# External_Memory.net
KiCad netlist of a schematic drawn in Altium Designer
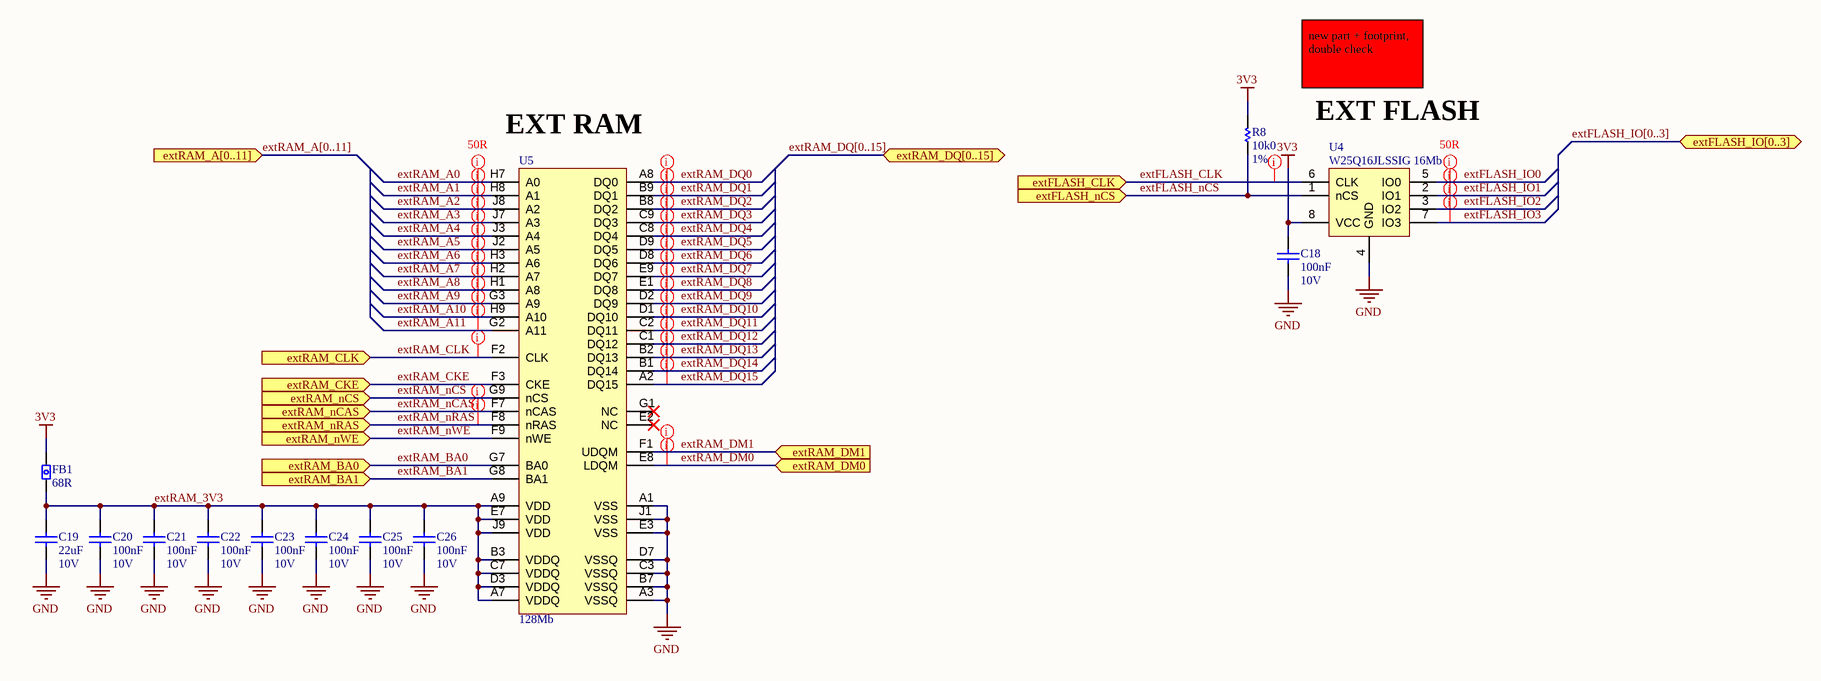
[diagram p0: External Memory.SchDoc]

(export (version "E")
  (design (tool "Eeschema 10.0.6"))
  (components
    (comp (ref "C18")
      (value "100nF")
      (footprint "C0201")
      (description "CAP CER 0.1UF 10V X5R 0201")
      (fields (field (name "TOLERANCE") "20%") (field (name "VOLTAGE RATING") "10V"))
      (libsource (lib "MCU") (part "CAP CER 100nF 10V X5R 0201"))
    )
    (comp (ref "C19")
      (value "22uF")
      (footprint "c0603")
      (description "0603 22 uF 10 V ±20% Tolerance X5R Multilayer Ceramic Chip Capacitor")
      (fields
        (field (name "MANUFACTURER") "Murata")
        (field (name "MANUFACTURER PART NUMBER") "GRM188R61A226ME15D")
        (field (name "VOLTAGE RATING") "10V")
      )
      (libsource (lib "MCU") (part "CAP CER 22uF 10V X5R 0603"))
    )
    (comp (ref "C20")
      (value "100nF")
      (footprint "C0201")
      (description "CAP CER 0.1UF 10V X5R 0201")
      (fields (field (name "TOLERANCE") "20%") (field (name "VOLTAGE RATING") "10V"))
      (libsource (lib "MCU") (part "CAP CER 100nF 10V X5R 0201"))
    )
    (comp (ref "C21")
      (value "100nF")
      (footprint "C0201")
      (description "CAP CER 0.1UF 10V X5R 0201")
      (fields (field (name "TOLERANCE") "20%") (field (name "VOLTAGE RATING") "10V"))
      (libsource (lib "MCU") (part "CAP CER 100nF 10V X5R 0201"))
    )
    (comp (ref "C22")
      (value "100nF")
      (footprint "C0201")
      (description "CAP CER 0.1UF 10V X5R 0201")
      (fields (field (name "TOLERANCE") "20%") (field (name "VOLTAGE RATING") "10V"))
      (libsource (lib "MCU") (part "CAP CER 100nF 10V X5R 0201"))
    )
    (comp (ref "C23")
      (value "100nF")
      (footprint "C0201")
      (description "CAP CER 0.1UF 10V X5R 0201")
      (fields (field (name "TOLERANCE") "20%") (field (name "VOLTAGE RATING") "10V"))
      (libsource (lib "MCU") (part "CAP CER 100nF 10V X5R 0201"))
    )
    (comp (ref "C24")
      (value "100nF")
      (footprint "C0201")
      (description "CAP CER 0.1UF 10V X5R 0201")
      (fields (field (name "TOLERANCE") "20%") (field (name "VOLTAGE RATING") "10V"))
      (libsource (lib "MCU") (part "CAP CER 100nF 10V X5R 0201"))
    )
    (comp (ref "C25")
      (value "100nF")
      (footprint "C0201")
      (description "CAP CER 0.1UF 10V X5R 0201")
      (fields (field (name "TOLERANCE") "20%") (field (name "VOLTAGE RATING") "10V"))
      (libsource (lib "MCU") (part "CAP CER 100nF 10V X5R 0201"))
    )
    (comp (ref "C26")
      (value "100nF")
      (footprint "C0201")
      (description "CAP CER 0.1UF 10V X5R 0201")
      (fields (field (name "TOLERANCE") "20%") (field (name "VOLTAGE RATING") "10V"))
      (libsource (lib "MCU") (part "CAP CER 100nF 10V X5R 0201"))
    )
    (comp (ref "FB1")
      (value "68R")
      (footprint "FB0402")
      (description "Ferrite Beads Multi-Layer 68Ohm 25% 100MHz 400mA 310mOhm DCR 0402 T/R")
      (fields
        (field (name "MANUFACTURER") "Taiyo Yuden")
        (field (name "MANUFACTURER PART NUMBER") "BK1005LL680-T")
      )
      (libsource (lib "MCU") (part "FB 68R 400mA 310mR 0402"))
    )
    (comp (ref "R8")
      (value "10k0")
      (footprint "r0402")
      (description "Res General Purpose Thick Film 0402 10K Ohm 1% 1/16W ±100ppm/°C Molded SMD Paper T/R")
      (fields
        (field (name "MANUFACTURER") "Yageo")
        (field (name "MANUFACTURER PART NUMBER") "RC0402FR-0710KL")
        (field (name "TOLERANCE") "1%")
      )
      (libsource (lib "MCU") (part "RES 10k0 1% 63mW 0402"))
    )
    (comp (ref "U4")
      (value "W25Q16JLSSIG 16Mb")
      (footprint "SOC8W 7.9x5.3mm")
      (description "NOR Flash Serial (SPI, Dual SPI, Quad SPI) 2.5V/3.3V 16M-bit 2M x 8 6ns 8-Pin SOIC Tube")
      (fields
        (field (name "MANUFACTURER") "Winbond")
        (field (name "MANUFACTURER PART NUMBER") "W25Q16JLSSIG")
      )
      (libsource (lib "MCU") (part "IC FLASH QSPI 16Mb W25Q16JLSSIG"))
    )
    (comp (ref "U5")
      (value "128Mb")
      (footprint "TFBGA54 8x8 SDRAM")
      (description "SDR 128Mb 8M x 16 3.3V 54ball BGA 166 Mhz Tape and Reel")
      (fields
        (field (name "MANUFACTURER") "Alliance Memory")
        (field (name "MANUFACTURER PART NUMBER") "AS4C8M16SA-6BINTR")
      )
      (libsource (lib "MCU") (part "IC MEM SDRAM 128MB 54BGA AS4C8M16SA-6BINTR"))
    )
  )
  (nets
    (net (code "1") (name "/extFLASH_CLK") (class "Default")
      (node (ref "U4") (pin "6") (pinfunction "CLK_6") (pintype "passive"))
    )
    (net (code "2") (name "/extFLASH_IO0") (class "Default")
      (node (ref "U4") (pin "5") (pinfunction "IO0_5") (pintype "passive"))
    )
    (net (code "3") (name "/extFLASH_IO1") (class "Default")
      (node (ref "U4") (pin "2") (pinfunction "IO1_2") (pintype "passive"))
    )
    (net (code "4") (name "/extFLASH_IO2") (class "Default")
      (node (ref "U4") (pin "3") (pinfunction "IO2_3") (pintype "passive"))
    )
    (net (code "5") (name "/extFLASH_IO3") (class "Default")
      (node (ref "U4") (pin "7") (pinfunction "IO3_7") (pintype "passive"))
    )
    (net (code "7") (name "/extFLASH_nCS") (class "Default")
      (node (ref "R8") (pin "1") (pinfunction "1_1") (pintype "passive"))
      (node (ref "U4") (pin "1") (pinfunction "nCS_1") (pintype "passive"))
    )
    (net (code "8") (name "/extRAM_3V3") (class "Default")
      (node (ref "C19") (pin "2") (pinfunction "2_2") (pintype "passive"))
      (node (ref "C20") (pin "2") (pinfunction "2_2") (pintype "passive"))
      (node (ref "C21") (pin "2") (pinfunction "2_2") (pintype "passive"))
      (node (ref "C22") (pin "2") (pinfunction "2_2") (pintype "passive"))
      (node (ref "C23") (pin "2") (pinfunction "2_2") (pintype "passive"))
      (node (ref "C24") (pin "2") (pinfunction "2_2") (pintype "passive"))
      (node (ref "C25") (pin "2") (pinfunction "2_2") (pintype "passive"))
      (node (ref "C26") (pin "2") (pinfunction "2_2") (pintype "passive"))
      (node (ref "FB1") (pin "1") (pintype "passive"))
      (node (ref "U5") (pin "A7") (pinfunction "VDDQ_A7") (pintype "passive"))
      (node (ref "U5") (pin "A9") (pinfunction "VDD_A9") (pintype "passive"))
      (node (ref "U5") (pin "B3") (pinfunction "VDDQ_B3") (pintype "passive"))
      (node (ref "U5") (pin "C7") (pinfunction "VDDQ_C7") (pintype "passive"))
      (node (ref "U5") (pin "D3") (pinfunction "VDDQ_D3") (pintype "passive"))
      (node (ref "U5") (pin "E7") (pinfunction "VDD_E7") (pintype "passive"))
      (node (ref "U5") (pin "J9") (pinfunction "VDD_J9") (pintype "passive"))
    )
    (net (code "9") (name "/extRAM_A0") (class "Default")
      (node (ref "U5") (pin "H7") (pinfunction "A0_H7") (pintype "passive"))
    )
    (net (code "10") (name "/extRAM_A1") (class "Default")
      (node (ref "U5") (pin "H8") (pinfunction "A1_H8") (pintype "passive"))
    )
    (net (code "11") (name "/extRAM_A2") (class "Default")
      (node (ref "U5") (pin "J8") (pinfunction "A2_J8") (pintype "passive"))
    )
    (net (code "12") (name "/extRAM_A3") (class "Default")
      (node (ref "U5") (pin "J7") (pinfunction "A3_J7") (pintype "passive"))
    )
    (net (code "13") (name "/extRAM_A4") (class "Default")
      (node (ref "U5") (pin "J3") (pinfunction "A4_J3") (pintype "passive"))
    )
    (net (code "14") (name "/extRAM_A5") (class "Default")
      (node (ref "U5") (pin "J2") (pinfunction "A5_J2") (pintype "passive"))
    )
    (net (code "15") (name "/extRAM_A6") (class "Default")
      (node (ref "U5") (pin "H3") (pinfunction "A6_H3") (pintype "passive"))
    )
    (net (code "16") (name "/extRAM_A7") (class "Default")
      (node (ref "U5") (pin "H2") (pinfunction "A7_H2") (pintype "passive"))
    )
    (net (code "17") (name "/extRAM_A8") (class "Default")
      (node (ref "U5") (pin "H1") (pinfunction "A8_H1") (pintype "passive"))
    )
    (net (code "18") (name "/extRAM_A9") (class "Default")
      (node (ref "U5") (pin "G3") (pinfunction "A9_G3") (pintype "passive"))
    )
    (net (code "19") (name "/extRAM_A10") (class "Default")
      (node (ref "U5") (pin "H9") (pinfunction "A10_H9") (pintype "passive"))
    )
    (net (code "20") (name "/extRAM_A11") (class "Default")
      (node (ref "U5") (pin "G2") (pinfunction "A11_G2") (pintype "passive"))
    )
    (net (code "22") (name "/extRAM_BA0") (class "Default")
      (node (ref "U5") (pin "G7") (pinfunction "BA0_G7") (pintype "passive"))
    )
    (net (code "23") (name "/extRAM_BA1") (class "Default")
      (node (ref "U5") (pin "G8") (pinfunction "BA1_G8") (pintype "passive"))
    )
    (net (code "24") (name "/extRAM_CKE") (class "Default")
      (node (ref "U5") (pin "F3") (pinfunction "CKE_F3") (pintype "passive"))
    )
    (net (code "25") (name "/extRAM_CLK") (class "Default")
      (node (ref "U5") (pin "F2") (pinfunction "CLK_F2") (pintype "passive"))
    )
    (net (code "26") (name "/extRAM_DM0") (class "Default")
      (node (ref "U5") (pin "E8") (pinfunction "LDQM_E8") (pintype "passive"))
    )
    (net (code "27") (name "/extRAM_DM1") (class "Default")
      (node (ref "U5") (pin "F1") (pinfunction "UDQM_F1") (pintype "passive"))
    )
    (net (code "28") (name "/extRAM_DQ0") (class "Default")
      (node (ref "U5") (pin "A8") (pinfunction "DQ0_A8") (pintype "passive"))
    )
    (net (code "29") (name "/extRAM_DQ1") (class "Default")
      (node (ref "U5") (pin "B9") (pinfunction "DQ1_B9") (pintype "passive"))
    )
    (net (code "30") (name "/extRAM_DQ2") (class "Default")
      (node (ref "U5") (pin "B8") (pinfunction "DQ2_B8") (pintype "passive"))
    )
    (net (code "31") (name "/extRAM_DQ3") (class "Default")
      (node (ref "U5") (pin "C9") (pinfunction "DQ3_C9") (pintype "passive"))
    )
    (net (code "32") (name "/extRAM_DQ4") (class "Default")
      (node (ref "U5") (pin "C8") (pinfunction "DQ4_C8") (pintype "passive"))
    )
    (net (code "33") (name "/extRAM_DQ5") (class "Default")
      (node (ref "U5") (pin "D9") (pinfunction "DQ5_D9") (pintype "passive"))
    )
    (net (code "34") (name "/extRAM_DQ6") (class "Default")
      (node (ref "U5") (pin "D8") (pinfunction "DQ6_D8") (pintype "passive"))
    )
    (net (code "35") (name "/extRAM_DQ7") (class "Default")
      (node (ref "U5") (pin "E9") (pinfunction "DQ7_E9") (pintype "passive"))
    )
    (net (code "36") (name "/extRAM_DQ8") (class "Default")
      (node (ref "U5") (pin "E1") (pinfunction "DQ8_E1") (pintype "passive"))
    )
    (net (code "37") (name "/extRAM_DQ9") (class "Default")
      (node (ref "U5") (pin "D2") (pinfunction "DQ9_D2") (pintype "passive"))
    )
    (net (code "38") (name "/extRAM_DQ10") (class "Default")
      (node (ref "U5") (pin "D1") (pinfunction "DQ10_D1") (pintype "passive"))
    )
    (net (code "39") (name "/extRAM_DQ11") (class "Default")
      (node (ref "U5") (pin "C2") (pinfunction "DQ11_C2") (pintype "passive"))
    )
    (net (code "40") (name "/extRAM_DQ12") (class "Default")
      (node (ref "U5") (pin "C1") (pinfunction "DQ12_C1") (pintype "passive"))
    )
    (net (code "41") (name "/extRAM_DQ13") (class "Default")
      (node (ref "U5") (pin "B2") (pinfunction "DQ13_B2") (pintype "passive"))
    )
    (net (code "42") (name "/extRAM_DQ14") (class "Default")
      (node (ref "U5") (pin "B1") (pinfunction "DQ14_B1") (pintype "passive"))
    )
    (net (code "43") (name "/extRAM_DQ15") (class "Default")
      (node (ref "U5") (pin "A2") (pinfunction "DQ15_A2") (pintype "passive"))
    )
    (net (code "45") (name "/extRAM_nCAS") (class "Default")
      (node (ref "U5") (pin "F7") (pinfunction "nCAS_F7") (pintype "passive"))
    )
    (net (code "46") (name "/extRAM_nCS") (class "Default")
      (node (ref "U5") (pin "G9") (pinfunction "nCS_G9") (pintype "passive"))
    )
    (net (code "47") (name "/extRAM_nRAS") (class "Default")
      (node (ref "U5") (pin "F8") (pinfunction "nRAS_F8") (pintype "passive"))
    )
    (net (code "48") (name "/extRAM_nWE") (class "Default")
      (node (ref "U5") (pin "F9") (pinfunction "nWE_F9") (pintype "passive"))
    )
    (net (code "49") (name "3V3") (class "Default")
      (node (ref "C18") (pin "2") (pinfunction "2_2") (pintype "passive"))
      (node (ref "FB1") (pin "2") (pintype "passive"))
      (node (ref "R8") (pin "2") (pinfunction "2_2") (pintype "passive"))
      (node (ref "U4") (pin "8") (pinfunction "VCC_8") (pintype "passive"))
    )
    (net (code "50") (name "GND") (class "Default")
      (node (ref "C18") (pin "1") (pinfunction "1_1") (pintype "passive"))
      (node (ref "C19") (pin "1") (pinfunction "1_1") (pintype "passive"))
      (node (ref "C20") (pin "1") (pinfunction "1_1") (pintype "passive"))
      (node (ref "C21") (pin "1") (pinfunction "1_1") (pintype "passive"))
      (node (ref "C22") (pin "1") (pinfunction "1_1") (pintype "passive"))
      (node (ref "C23") (pin "1") (pinfunction "1_1") (pintype "passive"))
      (node (ref "C24") (pin "1") (pinfunction "1_1") (pintype "passive"))
      (node (ref "C25") (pin "1") (pinfunction "1_1") (pintype "passive"))
      (node (ref "C26") (pin "1") (pinfunction "1_1") (pintype "passive"))
      (node (ref "U4") (pin "4") (pinfunction "GND_4") (pintype "passive"))
      (node (ref "U5") (pin "A1") (pinfunction "VSS_A1") (pintype "passive"))
      (node (ref "U5") (pin "A3") (pinfunction "VSSQ_A3") (pintype "passive"))
      (node (ref "U5") (pin "B7") (pinfunction "VSSQ_B7") (pintype "passive"))
      (node (ref "U5") (pin "C3") (pinfunction "VSSQ_C3") (pintype "passive"))
      (node (ref "U5") (pin "D7") (pinfunction "VSSQ_D7") (pintype "passive"))
      (node (ref "U5") (pin "E3") (pinfunction "VSS_E3") (pintype "passive"))
      (node (ref "U5") (pin "J1") (pinfunction "VSS_J1") (pintype "passive"))
    )
    (net (code "51") (name "unconnected-(U5-NC-PadE2)") (class "Default")
      (node (ref "U5") (pin "E2") (pinfunction "NC_E2") (pintype "passive+no_connect"))
    )
    (net (code "52") (name "unconnected-(U5-NC-PadG1)") (class "Default")
      (node (ref "U5") (pin "G1") (pinfunction "NC_G1") (pintype "passive+no_connect"))
    )
  )
)
